# P5V_Regulator.net
KiCad netlist of a schematic drawn in Altium Designer
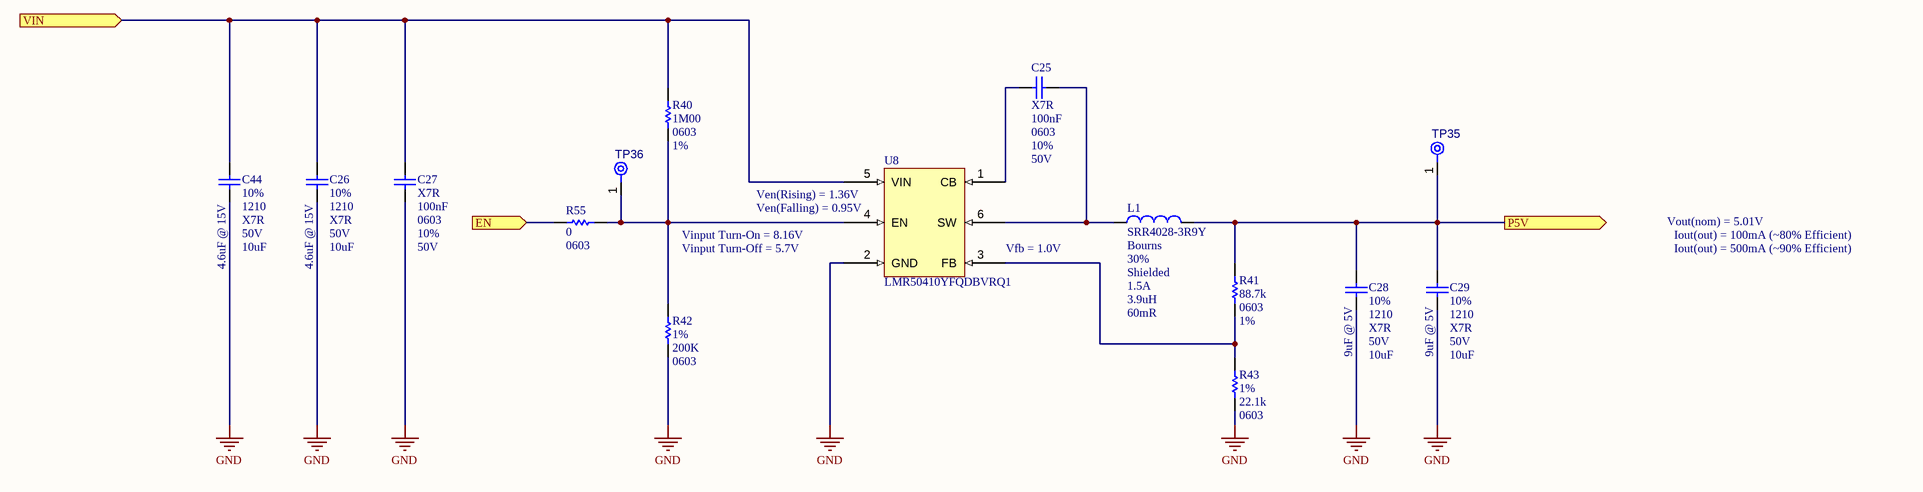
[diagram p0: P5V_Regulator.SchDoc]

(export (version "E")
  (design (tool "Eeschema 10.0.6"))
  (components
    (comp (ref "C25")
      (value "100nF")
      (footprint "CAPC1608X90X40ML10T20")
      (description "Chip Capacitor, 100nF, +/- 10%, 50 V, X7R 0603 (1608 Metric)")
      (fields
        (field (name "DIELECTRIC") "X7R")
        (field (name "CASE/PACKAGE") "0603")
        (field (name "TOLERANCE") "10%")
        (field (name "VOLTAGE RATING") "50V")
        (field (name "Comment") "Capacitor 100nF +/- 10%, 50V, X7R, 0603")
      )
      (libsource (lib "Applied Physics Lab") (part "CAP-NP-2"))
    )
    (comp (ref "C26")
      (value "10uF")
      (footprint "CAPC3225X270X30ML30")
      (description "Chip Capacitor, 10uF, 10%, 50 V, X7R 1210 (3225 Metric)")
      (fields
        (field (name "TOLERANCE") "10%")
        (field (name "CASE/PACKAGE") "1210")
        (field (name "DIELECTRIC") "X7R")
        (field (name "VOLTAGE RATING") "50V")
        (field (name "Comment") "Capacitor 10uF 10%, 50V, X7R, 1210")
      )
      (libsource (lib "Applied Physics Lab") (part "CAP-NP-2"))
    )
    (comp (ref "C27")
      (value "100nF")
      (footprint "CAPC1608X90X40ML10T20")
      (description "Chip Capacitor, 100nF, +/- 10%, 50 V, X7R 0603 (1608 Metric)")
      (fields
        (field (name "DIELECTRIC") "X7R")
        (field (name "CASE/PACKAGE") "0603")
        (field (name "TOLERANCE") "10%")
        (field (name "VOLTAGE RATING") "50V")
        (field (name "Comment") "Capacitor 100nF +/- 10%, 50V, X7R, 0603")
      )
      (libsource (lib "Applied Physics Lab") (part "CAP-NP-2"))
    )
    (comp (ref "C28")
      (value "10uF")
      (footprint "CAPC3225X270X30ML30")
      (description "Chip Capacitor, 10uF, 10%, 50 V, X7R 1210 (3225 Metric)")
      (fields
        (field (name "TOLERANCE") "10%")
        (field (name "CASE/PACKAGE") "1210")
        (field (name "DIELECTRIC") "X7R")
        (field (name "VOLTAGE RATING") "50V")
        (field (name "Comment") "Capacitor 10uF 10%, 50V, X7R, 1210")
      )
      (libsource (lib "Applied Physics Lab") (part "CAP-NP-2"))
    )
    (comp (ref "C29")
      (value "10uF")
      (footprint "CAPC3225X270X30ML30")
      (description "Chip Capacitor, 10uF, 10%, 50 V, X7R 1210 (3225 Metric)")
      (fields
        (field (name "TOLERANCE") "10%")
        (field (name "CASE/PACKAGE") "1210")
        (field (name "DIELECTRIC") "X7R")
        (field (name "VOLTAGE RATING") "50V")
        (field (name "Comment") "Capacitor 10uF 10%, 50V, X7R, 1210")
      )
      (libsource (lib "Applied Physics Lab") (part "CAP-NP-2"))
    )
    (comp (ref "C44")
      (value "10uF")
      (footprint "CAPC3225X270X30ML30")
      (description "Chip Capacitor, 10uF, 10%, 50 V, X7R 1210 (3225 Metric)")
      (fields
        (field (name "TOLERANCE") "10%")
        (field (name "CASE/PACKAGE") "1210")
        (field (name "DIELECTRIC") "X7R")
        (field (name "VOLTAGE RATING") "50V")
        (field (name "Comment") "Capacitor 10uF 10%, 50V, X7R, 1210")
      )
      (libsource (lib "Applied Physics Lab") (part "CAP-NP-2"))
    )
    (comp (ref "L1")
      (value "SRR4028-3R9Y")
      (footprint "INDP4848X30M")
      (description "Inductor Power Shielded Wirewound 3.9uH 30% 8.58 Q-Factor Ferrite 1.5A Saturation 60mROhm DCR")
      (fields
        (field (name "MANUFACTURER") "Bourns")
        (field (name "INDUCTANCE TOLERANCE") "30%")
        (field (name "SHIELDING") "Shielded")
        (field (name "SATURATION CURRENT") "1.5A")
        (field (name "INDUCTANCE") "3.9uH")
        (field (name "DC RESISTANCE (DCR)") "60mR")
      )
      (libsource (lib "Applied Physics Lab") (part "IND-2"))
    )
    (comp (ref "R40")
      (value "1M00")
      (footprint "RESC1609X50X30ML08T20")
      (description "Chip Resistor, 1M Ohm, +/- 1%, 0.1 W, -55 to 155 degC, 0603 (1608 Metric)")
      (fields
        (field (name "POWER") "100mW")
        (field (name "CASE/PACKAGE") "0603")
        (field (name "TOLERANCE") "1%")
        (field (name "Comment") "Resistor 1M +/-1% 0603 100 mW")
      )
      (libsource (lib "Applied Physics Lab") (part "RES-2"))
    )
    (comp (ref "R41")
      (value "88.7k")
      (footprint "RESC1608X55X25ML10T15")
      (description "Chip Resistor, 88.7k Ohm, +/- 1%, 0.1 W, -55 to 155 degC, 0603 (1608 Metric)")
      (fields
        (field (name "CASE/PACKAGE") "0603")
        (field (name "POWER") "100mW")
        (field (name "TOLERANCE") "1%")
        (field (name "Comment") "Resistor 88K7 +/-1% 0603 100 mW")
      )
      (libsource (lib "Applied Physics Lab") (part "RES-2"))
    )
    (comp (ref "R42")
      (value "200K")
      (footprint "RESC1609X50X30ML08T20")
      (description "Chip Resistor, 200k Ohm, +/- 1%, 0.1 W, -55 to 155 degC, 0603 (1608 Metric)")
      (fields
        (field (name "POWER") "100mW")
        (field (name "TOLERANCE") "1%")
        (field (name "CASE/PACKAGE") "0603")
        (field (name "Comment") "Resistor 200K +/-1% 0603 100 mW")
      )
      (libsource (lib "Applied Physics Lab") (part "RES-2"))
    )
    (comp (ref "R43")
      (value "22.1k")
      (footprint "RESC1608X55X25ML10T15")
      (description "Chip Resistor, 22.1k Ohm, +/- 1%, 0.1 W, -55 to 155 degC, 0603 (1608 Metric)")
      (fields
        (field (name "TOLERANCE") "1%")
        (field (name "POWER") "100mW")
        (field (name "CASE/PACKAGE") "0603")
        (field (name "Comment") "Resistor 22K1 +/-1% 0603 100 mW")
      )
      (libsource (lib "Applied Physics Lab") (part "RES-2"))
    )
    (comp (ref "R55")
      (value "0")
      (footprint "RESC1608X55X25ML10T15")
      (description "Chip Resistor, 0 Ohm, 0.1 W, -55 to 155 degC, 0603 (1608 Metric)")
      (fields
        (field (name "TOLERANCE") "5%")
        (field (name "CASE/PACKAGE") "0603")
        (field (name "POWER") "100mW")
      )
      (libsource (lib "Applied Physics Lab") (part "RES-2"))
    )
    (comp (ref "TP35")
      (value "TPAD6R-CIRCLED")
      (footprint "TP06R - Circled")
      (description "0.6mm round with a silkscreen circle.")
      (libsource (lib "Applied Physics Lab") (part "CMP-001-0001-4"))
    )
    (comp (ref "TP36")
      (value "TPAD6R-CIRCLED")
      (footprint "TP06R - Circled")
      (description "0.6mm round with a silkscreen circle.")
      (libsource (lib "Applied Physics Lab") (part "CMP-001-0001-4"))
    )
    (comp (ref "U8")
      (value "LMR50410YFQDBVRQ1")
      (footprint "SOT95P280X145-6M")
      (libsource (lib "Applied Physics Lab") (part "LMR50410YFQDBVRQ1-Symbol-1"))
    )
  )
  (nets
    (net (code "1") (name "/EN") (class "Default")
      (node (ref "R55") (pin "2") (pinfunction "2_2") (pintype "passive"))
    )
    (net (code "2") (name "/P5V") (class "Default")
      (node (ref "C28") (pin "2") (pinfunction "2_2") (pintype "passive"))
      (node (ref "C29") (pin "2") (pinfunction "2_2") (pintype "passive"))
      (node (ref "L1") (pin "2") (pinfunction "2_2") (pintype "passive"))
      (node (ref "R41") (pin "1") (pinfunction "1_1") (pintype "passive"))
      (node (ref "TP35") (pin "1") (pinfunction "TP_1") (pintype "passive"))
    )
    (net (code "3") (name "/VIN") (class "Default")
      (node (ref "C26") (pin "2") (pinfunction "2_2") (pintype "passive"))
      (node (ref "C27") (pin "2") (pinfunction "2_2") (pintype "passive"))
      (node (ref "C44") (pin "2") (pinfunction "2_2") (pintype "passive"))
      (node (ref "R40") (pin "2") (pinfunction "2_2") (pintype "passive"))
      (node (ref "U8") (pin "5") (pinfunction "VIN_5") (pintype "input"))
    )
    (net (code "4") (name "GND") (class "Default")
      (node (ref "C26") (pin "1") (pinfunction "1_1") (pintype "passive"))
      (node (ref "C27") (pin "1") (pinfunction "1_1") (pintype "passive"))
      (node (ref "C28") (pin "1") (pinfunction "1_1") (pintype "passive"))
      (node (ref "C29") (pin "1") (pinfunction "1_1") (pintype "passive"))
      (node (ref "C44") (pin "1") (pinfunction "1_1") (pintype "passive"))
      (node (ref "R42") (pin "1") (pinfunction "1_1") (pintype "passive"))
      (node (ref "R43") (pin "1") (pinfunction "1_1") (pintype "passive"))
      (node (ref "U8") (pin "2") (pinfunction "GND_2") (pintype "input"))
    )
    (net (code "5") (name "Net-(TP36-TP)") (class "Default")
      (node (ref "R40") (pin "1") (pinfunction "1_1") (pintype "passive"))
      (node (ref "R42") (pin "2") (pinfunction "2_2") (pintype "passive"))
      (node (ref "R55") (pin "1") (pinfunction "1_1") (pintype "passive"))
      (node (ref "TP36") (pin "1") (pinfunction "TP_1") (pintype "passive"))
      (node (ref "U8") (pin "4") (pinfunction "EN_4") (pintype "input"))
    )
    (net (code "6") (name "Net-(U8-CB)") (class "Default")
      (node (ref "C25") (pin "2") (pinfunction "2_2") (pintype "passive"))
      (node (ref "U8") (pin "1") (pinfunction "CB_1") (pintype "input"))
    )
    (net (code "7") (name "Net-(U8-FB)") (class "Default")
      (node (ref "R41") (pin "2") (pinfunction "2_2") (pintype "passive"))
      (node (ref "R43") (pin "2") (pinfunction "2_2") (pintype "passive"))
      (node (ref "U8") (pin "3") (pinfunction "FB_3") (pintype "input"))
    )
    (net (code "8") (name "Net-(U8-SW)") (class "Default")
      (node (ref "C25") (pin "1") (pinfunction "1_1") (pintype "passive"))
      (node (ref "L1") (pin "1") (pinfunction "1_1") (pintype "passive"))
      (node (ref "U8") (pin "6") (pinfunction "SW_6") (pintype "input"))
    )
  )
)
